# FPGA_Board_Top.net
KiCad netlist of a schematic drawn in Altium Designer
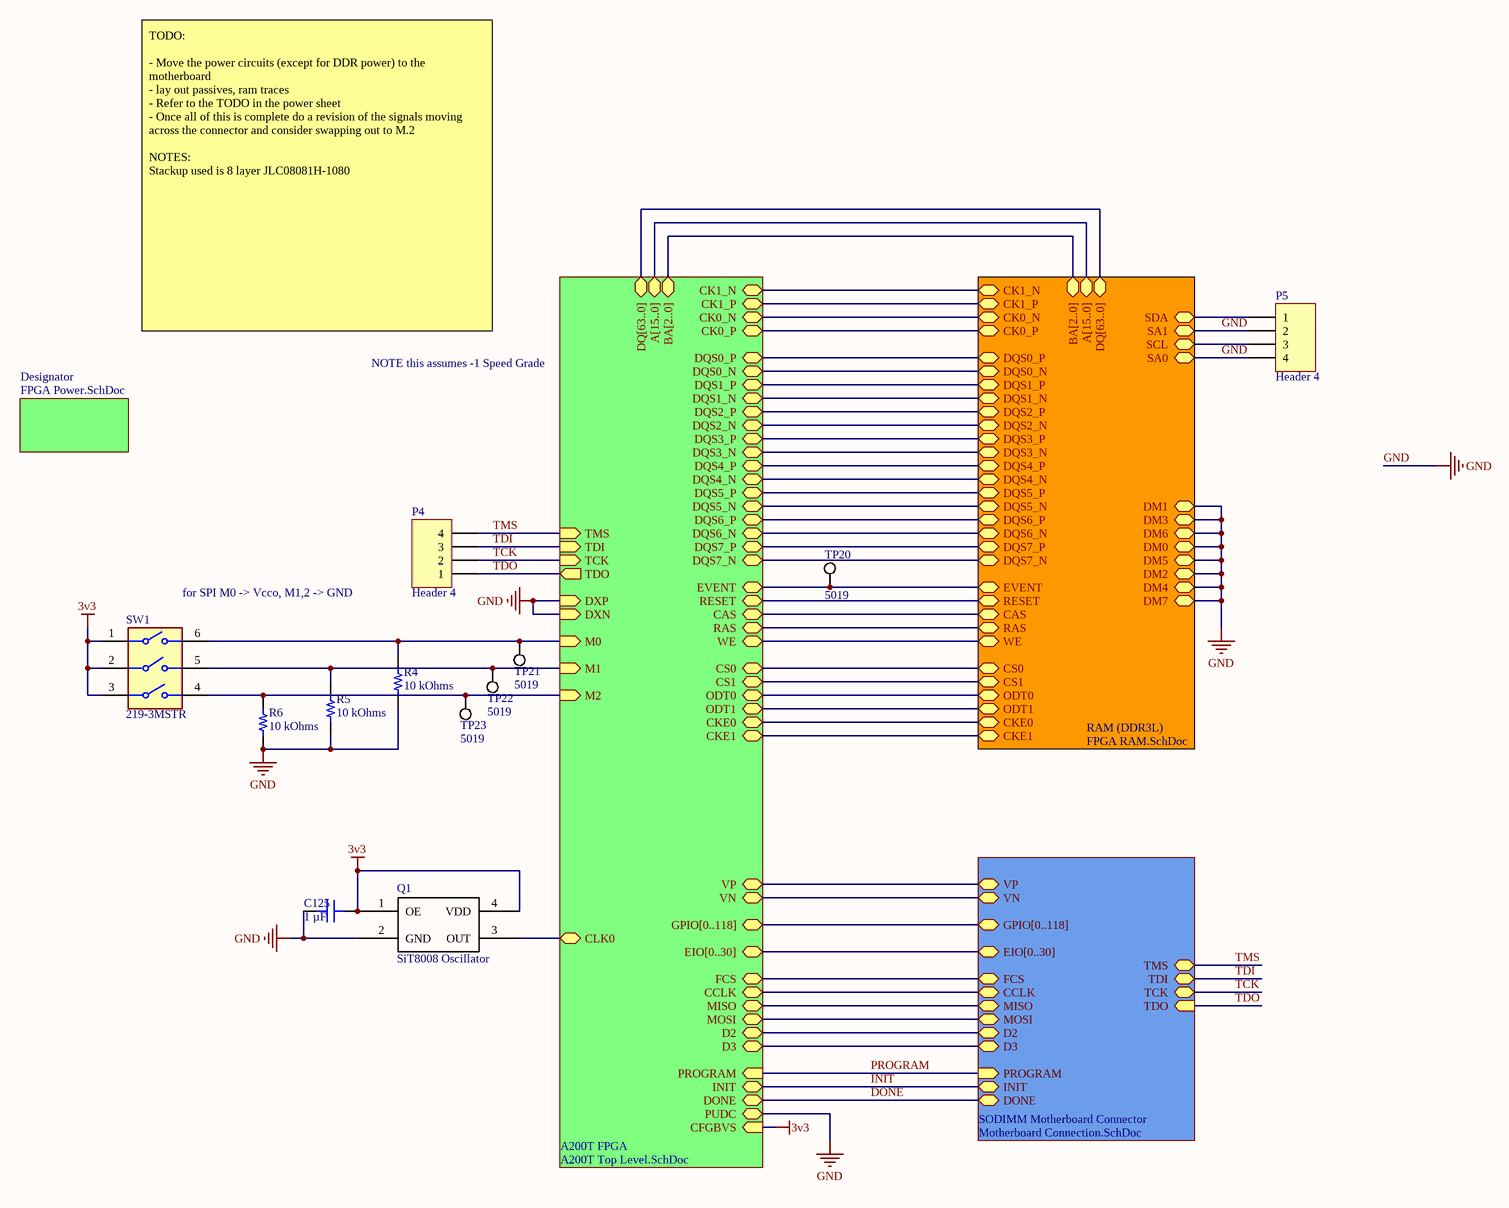
[diagram p0: FPGA Board Top.SchDoc]

(export (version "E")
  (design (tool "Eeschema 10.0.6"))
  (components
    (comp (ref "C125")
      (value "1 µF")
      (footprint "CAP 0603_1608")
      (description "CAP CER 1UF 25V X5R 0603")
      (fields
        (field (name "PART NUMBER") "CL10A105KA8NNNC")
        (field (name "MANUFACTURER") "Samsung Electro-Mechanics")
      )
      (libsource (lib "Celestial Altium Library - altium_library") (part "Capacitor"))
    )
    (comp (ref "P4")
      (value "Header 4")
      (footprint "HDR1X4")
      (description "Header, 4-Pin")
      (fields (field (name "PUBLISHER") "Altium Limited"))
      (libsource (lib "") (part "Header 4_1"))
    )
    (comp (ref "P5")
      (value "Header 4")
      (footprint "HDR1X4")
      (description "Header, 4-Pin")
      (fields (field (name "PUBLISHER") "Altium Limited"))
      (libsource (lib "Miscellaneous Connectors") (part "Header 4"))
    )
    (comp (ref "Q1")
      (value "SiT8008 Oscillator")
      (footprint "SiT8008 2.5x2")
      (libsource (lib "2020-09-26_17-27-19") (part "SiT8008 Oscillator"))
    )
    (comp (ref "R4")
      (value "10 kOhms")
      (footprint "RES 0603_1608")
      (description "RES 10K OHM 1% 1/10W 0603")
      (fields (field (name "PART NUMBER") "RC0603FR-0710KL") (field (name "MANUFACTURER") "Yageo"))
      (libsource (lib "Celestial Altium Library - altium_library") (part "Resistor"))
    )
    (comp (ref "R5")
      (value "10 kOhms")
      (footprint "RES 0603_1608")
      (description "RES 10K OHM 1% 1/10W 0603")
      (fields (field (name "PART NUMBER") "RC0603FR-0710KL") (field (name "MANUFACTURER") "Yageo"))
      (libsource (lib "Celestial Altium Library - altium_library") (part "Resistor"))
    )
    (comp (ref "R6")
      (value "10 kOhms")
      (footprint "RES 0603_1608")
      (description "RES 10K OHM 1% 1/10W 0603")
      (fields (field (name "PART NUMBER") "RC0603FR-0710KL") (field (name "MANUFACTURER") "Yageo"))
      (libsource (lib "Celestial Altium Library - altium_library") (part "Resistor"))
    )
    (comp (ref "SW1")
      (value "219-3MSTR")
      (footprint "FP-219-3MSTR-MFG")
      (description "SWITCH SLIDE DIP SPST 100MA 20V")
      (libsource (lib "Altium Content Vault") (part "7c490946f25aa2bb1cd4cef5bc3ec4e"))
    )
    (comp (ref "TP20")
      (value "5019")
      (footprint "KSTN-5019_V")
      (description "Test Point, 1 Position SMD, RoHS, Tape and Reel")
      (libsource (lib "Altium Content Vault") (part "TESTPOINT_WHITE"))
    )
    (comp (ref "TP21")
      (value "5019")
      (footprint "KSTN-5019_V")
      (description "Test Point, 1 Position SMD, RoHS, Tape and Reel")
      (libsource (lib "Altium Content Vault") (part "TESTPOINT_WHITE"))
    )
    (comp (ref "TP22")
      (value "5019")
      (footprint "KSTN-5019_V")
      (description "Test Point, 1 Position SMD, RoHS, Tape and Reel")
      (libsource (lib "Altium Content Vault") (part "TESTPOINT_WHITE"))
    )
    (comp (ref "TP23")
      (value "5019")
      (footprint "KSTN-5019_V")
      (description "Test Point, 1 Position SMD, RoHS, Tape and Reel")
      (libsource (lib "Altium Content Vault") (part "TESTPOINT_WHITE"))
    )
  )
  (nets
    (net (code "11") (name "/CLK0") (class "Default")
      (node (ref "Q1") (pin "3") (pinfunction "OUT_3") (pintype "passive"))
    )
    (net (code "35") (name "/EVENT") (class "Default")
      (node (ref "TP20") (pin "1") (pinfunction "1_1") (pintype "passive"))
    )
    (net (code "39") (name "/M0") (class "Default")
      (node (ref "R4") (pin "2") (pinfunction "2_2") (pintype "passive"))
      (node (ref "SW1") (pin "6") (pinfunction "6_6") (pintype "passive"))
      (node (ref "TP21") (pin "1") (pinfunction "1_1") (pintype "passive"))
    )
    (net (code "40") (name "/M1") (class "Default")
      (node (ref "R5") (pin "2") (pinfunction "2_2") (pintype "passive"))
      (node (ref "SW1") (pin "5") (pinfunction "5_5") (pintype "passive"))
      (node (ref "TP22") (pin "1") (pinfunction "1_1") (pintype "passive"))
    )
    (net (code "41") (name "/M2") (class "Default")
      (node (ref "R6") (pin "2") (pinfunction "2_2") (pintype "passive"))
      (node (ref "SW1") (pin "4") (pinfunction "4_4") (pintype "passive"))
      (node (ref "TP23") (pin "1") (pinfunction "1_1") (pintype "passive"))
    )
    (net (code "49") (name "/SCL") (class "Default")
      (node (ref "P5") (pin "3") (pinfunction "3_3") (pintype "passive"))
    )
    (net (code "50") (name "/SDA") (class "Default")
      (node (ref "P5") (pin "1") (pinfunction "1_1") (pintype "passive"))
    )
    (net (code "51") (name "/TCK") (class "Default")
      (node (ref "P4") (pin "2") (pinfunction "2_2") (pintype "passive"))
    )
    (net (code "52") (name "/TDI") (class "Default")
      (node (ref "P4") (pin "3") (pinfunction "3_3") (pintype "passive"))
    )
    (net (code "53") (name "/TDO") (class "Default")
      (node (ref "P4") (pin "1") (pinfunction "1_1") (pintype "passive"))
    )
    (net (code "54") (name "/TMS") (class "Default")
      (node (ref "P4") (pin "4") (pinfunction "4_4") (pintype "passive"))
    )
    (net (code "58") (name "3v3") (class "Default")
      (node (ref "C125") (pin "2") (pinfunction "2_2") (pintype "passive"))
      (node (ref "Q1") (pin "1") (pinfunction "OE_1") (pintype "passive"))
      (node (ref "Q1") (pin "4") (pinfunction "VDD_4") (pintype "passive"))
      (node (ref "SW1") (pin "1") (pinfunction "1_1") (pintype "passive"))
      (node (ref "SW1") (pin "2") (pinfunction "2_2") (pintype "passive"))
      (node (ref "SW1") (pin "3") (pinfunction "3_3") (pintype "passive"))
    )
    (net (code "59") (name "GND") (class "Default")
      (node (ref "C125") (pin "1") (pinfunction "1_1") (pintype "passive"))
      (node (ref "P5") (pin "2") (pinfunction "2_2") (pintype "passive"))
      (node (ref "P5") (pin "4") (pinfunction "4_4") (pintype "passive"))
      (node (ref "Q1") (pin "2") (pinfunction "GND_2") (pintype "passive"))
      (node (ref "R4") (pin "1") (pinfunction "1_1") (pintype "passive"))
      (node (ref "R5") (pin "1") (pinfunction "1_1") (pintype "passive"))
      (node (ref "R6") (pin "1") (pinfunction "1_1") (pintype "passive"))
    )
  )
)
